# BLE_v0_1a_prater_mod.net
KiCad netlist of a schematic drawn in EAGLE
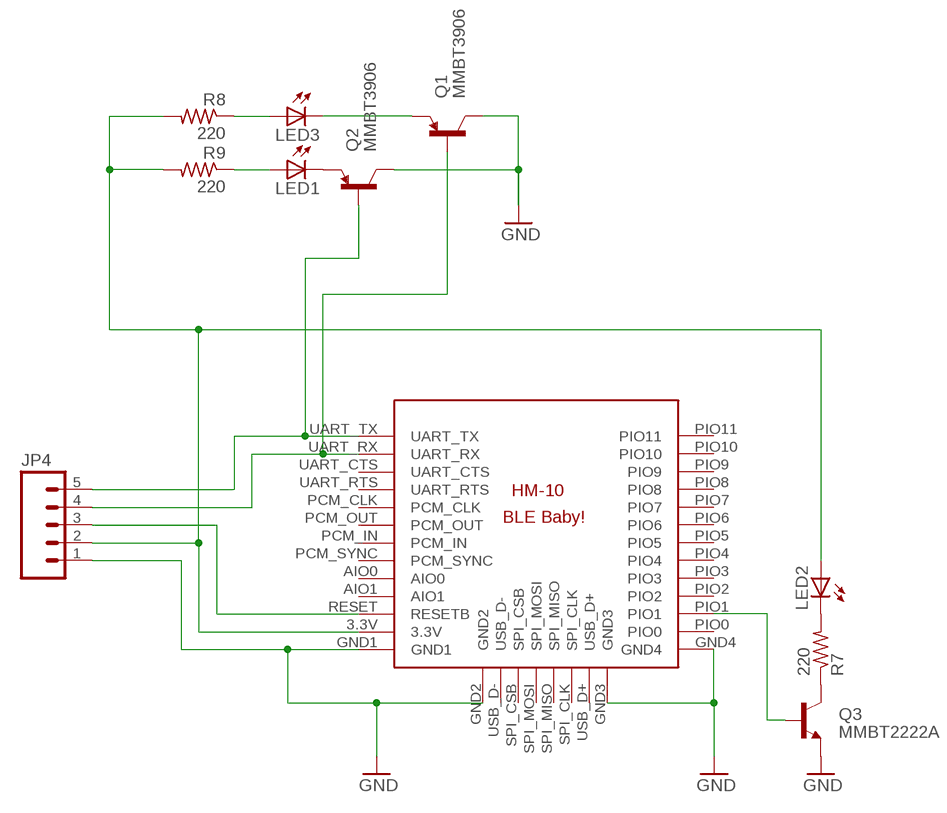
[diagram p0: schematic, sheet 1]

(export (version "E")
  (design (tool "Eeschema 10.0.6"))
  (components
    (comp (ref "JP4")
      (value "M05PTH")
      (footprint "eagle-import:1X05")
      (libsource (lib "eagle-import") (part "M05PTH"))
    )
    (comp (ref "LED1")
      (value "LED0603")
      (footprint "eagle-import:LED-0603")
      (libsource (lib "eagle-import") (part "LED0603"))
    )
    (comp (ref "LED2")
      (value "LED0603")
      (footprint "eagle-import:LED-0603")
      (libsource (lib "eagle-import") (part "LED0603"))
    )
    (comp (ref "LED3")
      (value "LED0603")
      (footprint "eagle-import:LED-0603")
      (libsource (lib "eagle-import") (part "LED0603"))
    )
    (comp (ref "Q1")
      (value "MMBT3906")
      (footprint "eagle-import:SOT23")
      (libsource (lib "eagle-import") (part "TRANSISTOR_PNPMMBT3906"))
    )
    (comp (ref "Q2")
      (value "MMBT3906")
      (footprint "eagle-import:SOT23")
      (libsource (lib "eagle-import") (part "TRANSISTOR_PNPMMBT3906"))
    )
    (comp (ref "Q3")
      (value "MMBT2222A")
      (footprint "eagle-import:SOT23")
      (libsource (lib "eagle-import") (part "TRANSISTOR_NPNMMBT2222A"))
    )
    (comp (ref "R7")
      (value "220")
      (footprint "eagle-import:M0805")
      (libsource (lib "eagle-import") (part "R-US_M0805"))
    )
    (comp (ref "R8")
      (value "220")
      (footprint "eagle-import:M0805")
      (libsource (lib "eagle-import") (part "R-US_M0805"))
    )
    (comp (ref "R9")
      (value "220")
      (footprint "eagle-import:M0805")
      (libsource (lib "eagle-import") (part "R-US_M0805"))
    )
    (comp (ref "U$1")
      (value "BLE-HM-10")
      (footprint "eagle-import:BLE-HM-10")
      (libsource (lib "eagle-import") (part "BLE-HM-10"))
    )
  )
  (nets
    (net (code "1") (name "GND") (class "Default")
      (node (ref "JP4") (pin "1") (pinfunction "1_1") (pintype "passive"))
      (node (ref "Q1") (pin "3") (pinfunction "C_3") (pintype "passive"))
      (node (ref "Q2") (pin "3") (pinfunction "C_3") (pintype "passive"))
      (node (ref "Q3") (pin "2") (pinfunction "E_2") (pintype "passive"))
      (node (ref "U$1") (pin "GND1") (pinfunction "GND1_GND1") (pintype "bidirectional"))
      (node (ref "U$1") (pin "GND2") (pinfunction "GND2_GND2") (pintype "bidirectional"))
      (node (ref "U$1") (pin "GND3") (pinfunction "GND3_GND3") (pintype "bidirectional"))
      (node (ref "U$1") (pin "GND4") (pinfunction "GND4_GND4") (pintype "bidirectional"))
    )
    (net (code "2") (name "Net-(JP4-Pad2)") (class "Default")
      (node (ref "JP4") (pin "2") (pinfunction "2_2") (pintype "passive"))
      (node (ref "LED2") (pin "A") (pinfunction "A_A") (pintype "passive"))
      (node (ref "R8") (pin "2") (pinfunction "2_2") (pintype "passive"))
      (node (ref "R9") (pin "2") (pinfunction "2_2") (pintype "passive"))
      (node (ref "U$1") (pin "3.3V") (pinfunction "3.3V_3.3V") (pintype "bidirectional"))
    )
    (net (code "3") (name "Net-(LED1-PadA)") (class "Default")
      (node (ref "LED1") (pin "A") (pinfunction "A_A") (pintype "passive"))
      (node (ref "R9") (pin "1") (pinfunction "1_1") (pintype "passive"))
    )
    (net (code "4") (name "Net-(LED2-PadC)") (class "Default")
      (node (ref "LED2") (pin "C") (pinfunction "C_C") (pintype "passive"))
      (node (ref "R7") (pin "2") (pinfunction "2_2") (pintype "passive"))
    )
    (net (code "5") (name "Net-(LED3-PadA)") (class "Default")
      (node (ref "LED3") (pin "A") (pinfunction "A_A") (pintype "passive"))
      (node (ref "R8") (pin "1") (pinfunction "1_1") (pintype "passive"))
    )
    (net (code "6") (name "Net-(Q1-B)") (class "Default")
      (node (ref "JP4") (pin "4") (pinfunction "4_4") (pintype "passive"))
      (node (ref "Q1") (pin "1") (pinfunction "B_1") (pintype "passive"))
      (node (ref "U$1") (pin "UART_RX") (pinfunction "UART_RX_UART_RX") (pintype "bidirectional"))
    )
    (net (code "7") (name "Net-(Q1-E)") (class "Default")
      (node (ref "LED3") (pin "C") (pinfunction "C_C") (pintype "passive"))
      (node (ref "Q1") (pin "2") (pinfunction "E_2") (pintype "passive"))
    )
    (net (code "8") (name "Net-(Q2-B)") (class "Default")
      (node (ref "JP4") (pin "5") (pinfunction "5_5") (pintype "passive"))
      (node (ref "Q2") (pin "1") (pinfunction "B_1") (pintype "passive"))
      (node (ref "U$1") (pin "UART_TX") (pinfunction "UART_TX_UART_TX") (pintype "bidirectional"))
    )
    (net (code "9") (name "Net-(Q2-E)") (class "Default")
      (node (ref "LED1") (pin "C") (pinfunction "C_C") (pintype "passive"))
      (node (ref "Q2") (pin "2") (pinfunction "E_2") (pintype "passive"))
    )
    (net (code "10") (name "Net-(Q3-B)") (class "Default")
      (node (ref "Q3") (pin "1") (pinfunction "B_1") (pintype "passive"))
      (node (ref "U$1") (pin "PIO1") (pinfunction "PIO1_PIO1") (pintype "bidirectional"))
    )
    (net (code "11") (name "Net-(Q3-C)") (class "Default")
      (node (ref "Q3") (pin "3") (pinfunction "C_3") (pintype "passive"))
      (node (ref "R7") (pin "1") (pinfunction "1_1") (pintype "passive"))
    )
    (net (code "12") (name "Net-(U$1-RESETB)") (class "Default")
      (node (ref "JP4") (pin "3") (pinfunction "3_3") (pintype "passive"))
      (node (ref "U$1") (pin "RESET") (pinfunction "RESETB_RESET") (pintype "bidirectional"))
    )
    (net (code "13") (name "unconnected-(U$1-PadAIO0)") (class "Default")
      (node (ref "U$1") (pin "AIO0") (pinfunction "AIO0_AIO0") (pintype "bidirectional"))
    )
    (net (code "14") (name "unconnected-(U$1-PadAIO1)") (class "Default")
      (node (ref "U$1") (pin "AIO1") (pinfunction "AIO1_AIO1") (pintype "bidirectional"))
    )
    (net (code "15") (name "unconnected-(U$1-PadPCM_CLK)") (class "Default")
      (node (ref "U$1") (pin "PCM_CLK") (pinfunction "PCM_CLK_PCM_CLK") (pintype "bidirectional"))
    )
    (net (code "16") (name "unconnected-(U$1-PadPCM_IN)") (class "Default")
      (node (ref "U$1") (pin "PCM_IN") (pinfunction "PCM_IN_PCM_IN") (pintype "bidirectional"))
    )
    (net (code "17") (name "unconnected-(U$1-PadPCM_OUT)") (class "Default")
      (node (ref "U$1") (pin "PCM_OUT") (pinfunction "PCM_OUT_PCM_OUT") (pintype "bidirectional"))
    )
    (net (code "18") (name "unconnected-(U$1-PadPCM_SYNC)") (class "Default")
      (node (ref "U$1") (pin "PCM_SYNC") (pinfunction "PCM_SYNC_PCM_SYNC") (pintype "bidirectional"))
    )
    (net (code "19") (name "unconnected-(U$1-PadPIO0)") (class "Default")
      (node (ref "U$1") (pin "PIO0") (pinfunction "PIO0_PIO0") (pintype "bidirectional"))
    )
    (net (code "20") (name "unconnected-(U$1-PadPIO2)") (class "Default")
      (node (ref "U$1") (pin "PIO2") (pinfunction "PIO2_PIO2") (pintype "bidirectional"))
    )
    (net (code "21") (name "unconnected-(U$1-PadPIO3)") (class "Default")
      (node (ref "U$1") (pin "PIO3") (pinfunction "PIO3_PIO3") (pintype "bidirectional"))
    )
    (net (code "22") (name "unconnected-(U$1-PadPIO4)") (class "Default")
      (node (ref "U$1") (pin "PIO4") (pinfunction "PIO4_PIO4") (pintype "bidirectional"))
    )
    (net (code "23") (name "unconnected-(U$1-PadPIO5)") (class "Default")
      (node (ref "U$1") (pin "PIO5") (pinfunction "PIO5_PIO5") (pintype "bidirectional"))
    )
    (net (code "24") (name "unconnected-(U$1-PadPIO6)") (class "Default")
      (node (ref "U$1") (pin "PIO6") (pinfunction "PIO6_PIO6") (pintype "bidirectional"))
    )
    (net (code "25") (name "unconnected-(U$1-PadPIO7)") (class "Default")
      (node (ref "U$1") (pin "PIO7") (pinfunction "PIO7_PIO7") (pintype "bidirectional"))
    )
    (net (code "26") (name "unconnected-(U$1-PadPIO8)") (class "Default")
      (node (ref "U$1") (pin "PIO8") (pinfunction "PIO8_PIO8") (pintype "bidirectional"))
    )
    (net (code "27") (name "unconnected-(U$1-PadPIO9)") (class "Default")
      (node (ref "U$1") (pin "PIO9") (pinfunction "PIO9_PIO9") (pintype "bidirectional"))
    )
    (net (code "28") (name "unconnected-(U$1-PadPIO10)") (class "Default")
      (node (ref "U$1") (pin "PIO10") (pinfunction "PIO10_PIO10") (pintype "bidirectional"))
    )
    (net (code "29") (name "unconnected-(U$1-PadPIO11)") (class "Default")
      (node (ref "U$1") (pin "PIO11") (pinfunction "PIO11_PIO11") (pintype "bidirectional"))
    )
    (net (code "30") (name "unconnected-(U$1-PadSPI_CLK)") (class "Default")
      (node (ref "U$1") (pin "SPI_CLK") (pinfunction "SPI_CLK_SPI_CLK") (pintype "bidirectional"))
    )
    (net (code "31") (name "unconnected-(U$1-PadSPI_CSB)") (class "Default")
      (node (ref "U$1") (pin "SPI_CSB") (pinfunction "SPI_CSB_SPI_CSB") (pintype "bidirectional"))
    )
    (net (code "32") (name "unconnected-(U$1-PadSPI_MISO)") (class "Default")
      (node (ref "U$1") (pin "SPI_MISO") (pinfunction "SPI_MISO_SPI_MISO") (pintype "bidirectional"))
    )
    (net (code "33") (name "unconnected-(U$1-PadSPI_MOSI)") (class "Default")
      (node (ref "U$1") (pin "SPI_MOSI") (pinfunction "SPI_MOSI_SPI_MOSI") (pintype "bidirectional"))
    )
    (net (code "34") (name "unconnected-(U$1-PadUART_CTS)") (class "Default")
      (node (ref "U$1") (pin "UART_CTS") (pinfunction "UART_CTS_UART_CTS") (pintype "bidirectional"))
    )
    (net (code "35") (name "unconnected-(U$1-PadUART_RTS)") (class "Default")
      (node (ref "U$1") (pin "UART_RTS") (pinfunction "UART_RTS_UART_RTS") (pintype "bidirectional"))
    )
    (net (code "36") (name "unconnected-(U$1-PadUSB_D+)") (class "Default")
      (node (ref "U$1") (pin "USB_D+") (pinfunction "USB_D+_USB_D+") (pintype "bidirectional"))
    )
    (net (code "37") (name "unconnected-(U$1-PadUSB_D-)") (class "Default")
      (node (ref "U$1") (pin "USB_D-") (pinfunction "USB_D-_USB_D-") (pintype "bidirectional"))
    )
  )
)
